# sokolov_control_board_2.net
KiCad netlist of a schematic drawn in Altium Designer
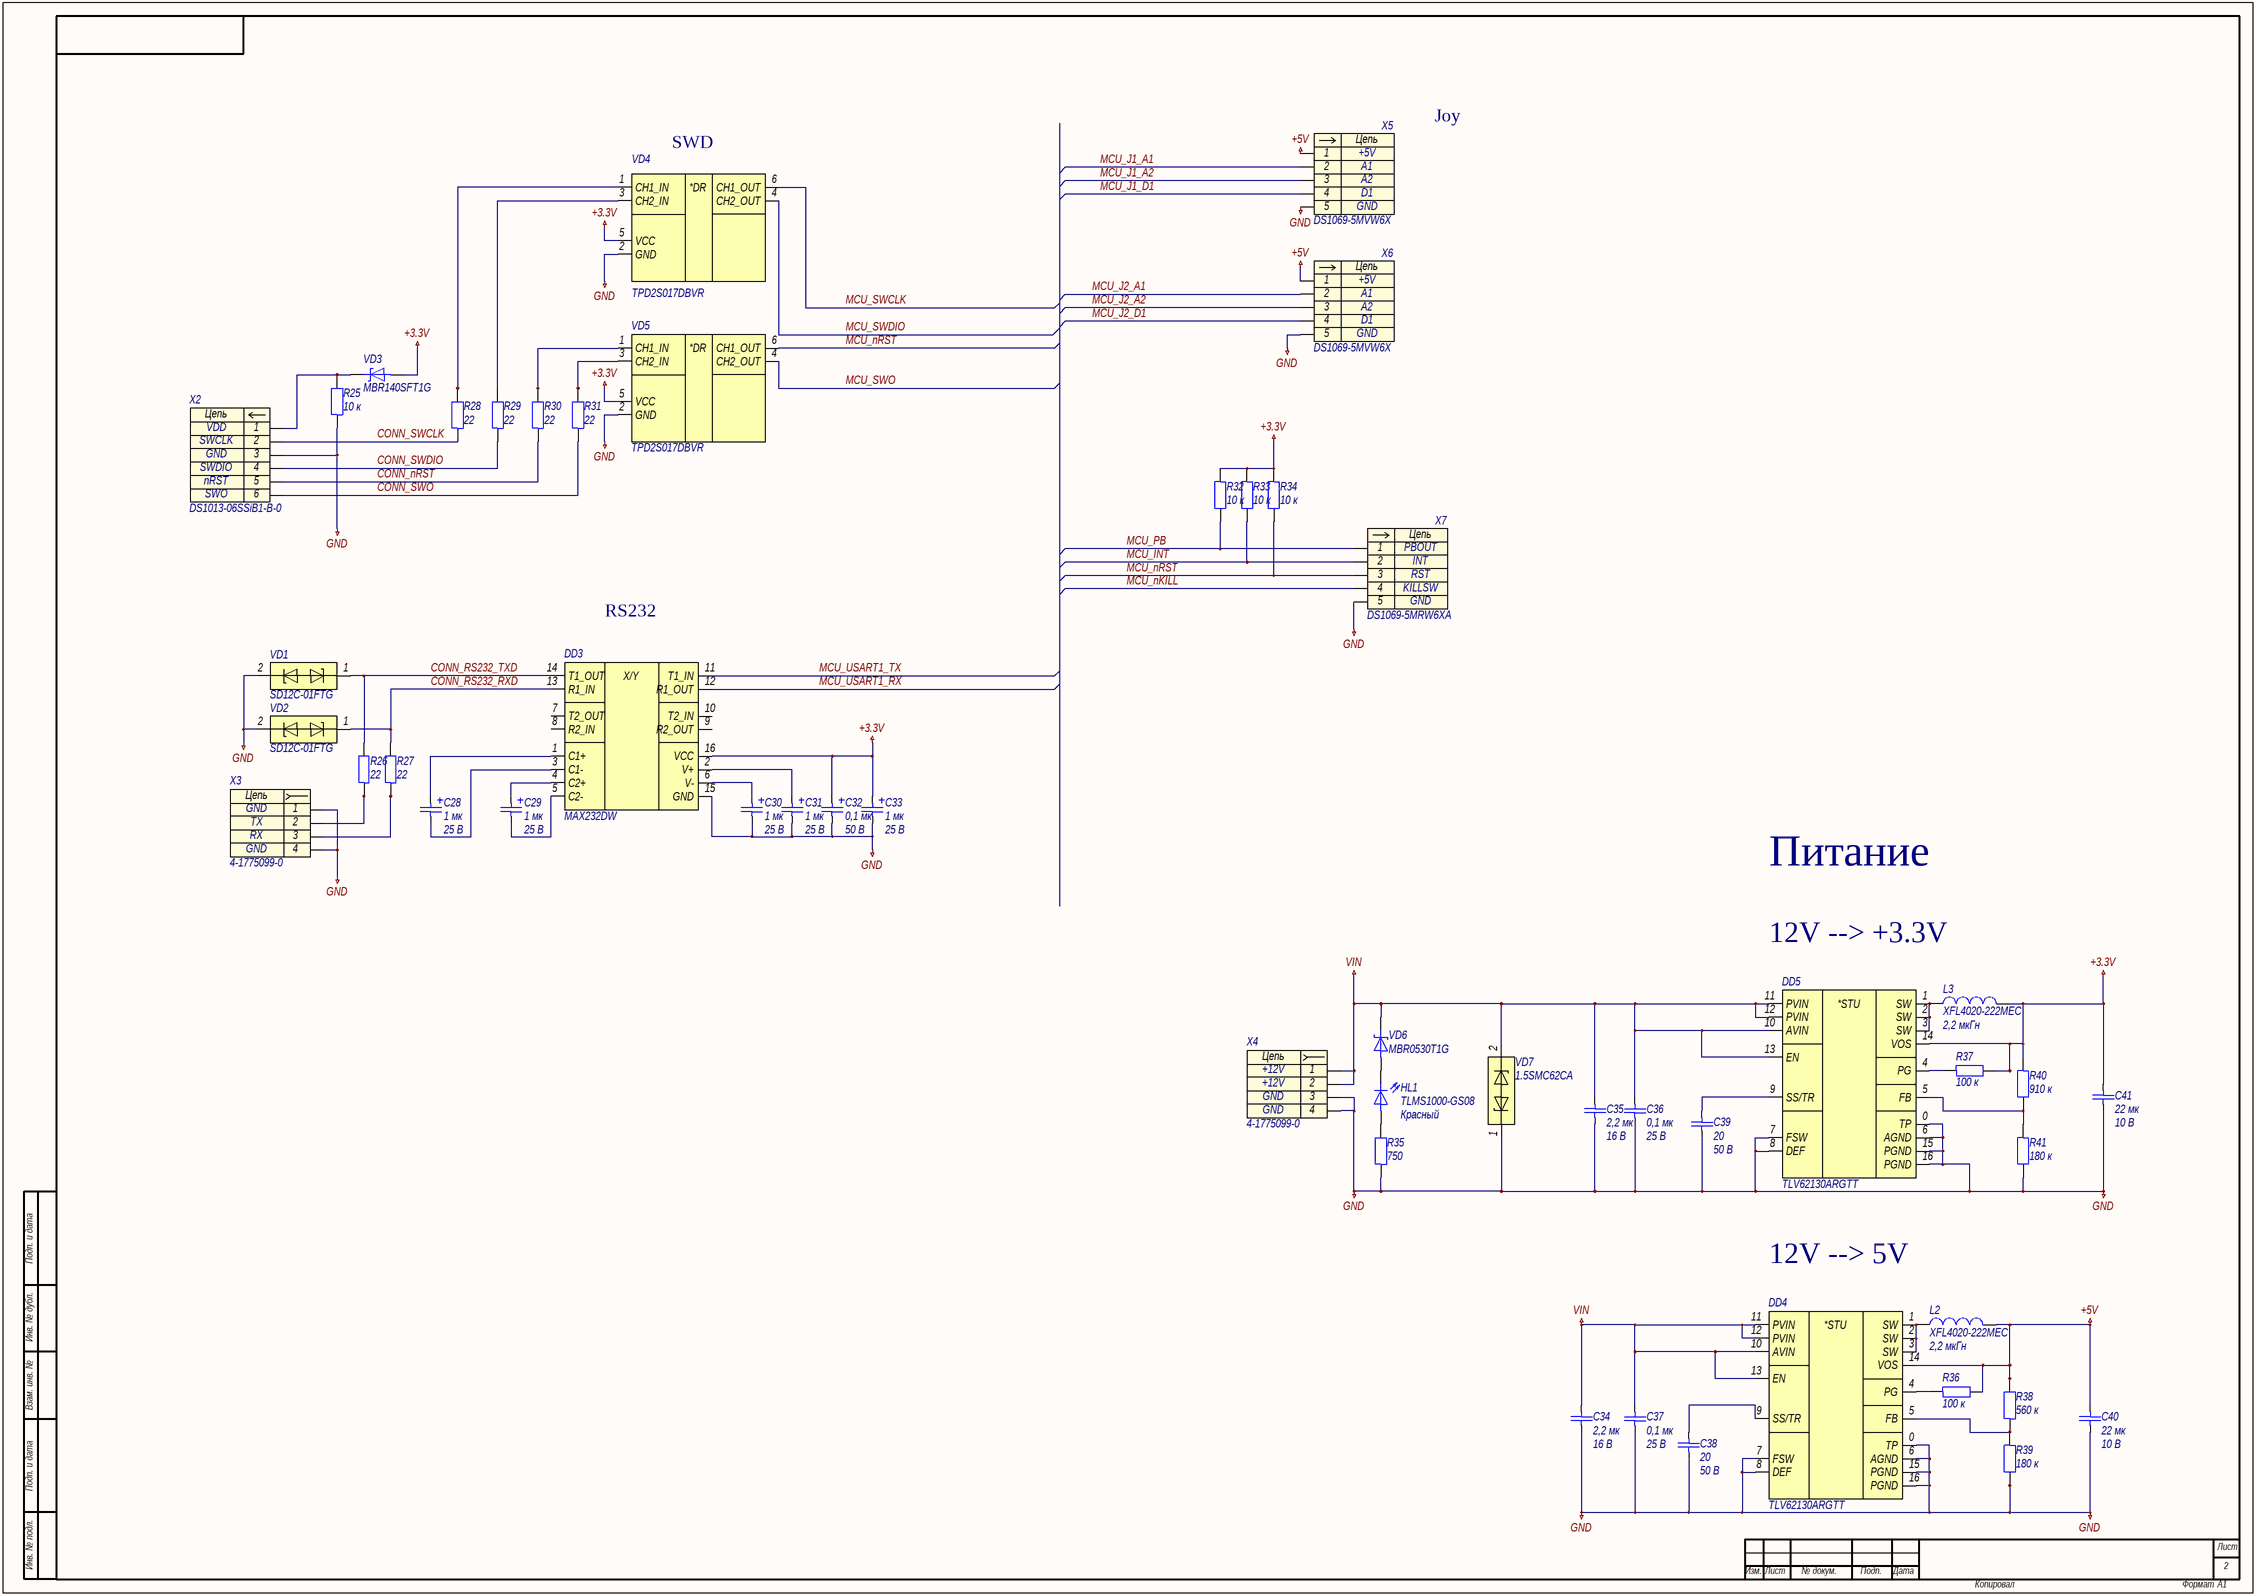
[diagram p0: sokolov_control_board_2.SchDoc]

(export (version "E")
  (design (tool "Eeschema 10.0.6"))
  (components
    (comp (ref "C28")
      (value "1 мк")
      (footprint "C3216-18")
      (description "=Описание")
      (fields (field (name "НАПРЯЖЕНИЕ") "25 В"))
      (libsource (lib "Database_Students") (part "CAPACITOR-POLAR"))
    )
    (comp (ref "C29")
      (value "1 мк")
      (footprint "C3216-18")
      (description "=Описание")
      (fields (field (name "НАПРЯЖЕНИЕ") "25 В"))
      (libsource (lib "Database_Students") (part "CAPACITOR-POLAR"))
    )
    (comp (ref "C30")
      (value "1 мк")
      (footprint "C3216-18")
      (description "=Описание")
      (fields (field (name "НАПРЯЖЕНИЕ") "25 В"))
      (libsource (lib "Database_Students") (part "CAPACITOR-POLAR"))
    )
    (comp (ref "C31")
      (value "1 мк")
      (footprint "C3216-18")
      (description "=Описание")
      (fields (field (name "НАПРЯЖЕНИЕ") "25 В"))
      (libsource (lib "Database_Students") (part "CAPACITOR-POLAR"))
    )
    (comp (ref "C32")
      (value "0,1 мк")
      (footprint "C3216-18")
      (description "=Описание")
      (fields (field (name "НАПРЯЖЕНИЕ") "50 В"))
      (libsource (lib "Database_Students") (part "CAPACITOR-POLAR"))
    )
    (comp (ref "C33")
      (value "1 мк")
      (footprint "C3216-18")
      (description "=Описание")
      (fields (field (name "НАПРЯЖЕНИЕ") "25 В"))
      (libsource (lib "Database_Students") (part "CAPACITOR-POLAR"))
    )
    (comp (ref "C34")
      (value "2,2 мк")
      (footprint "C0603")
      (description "=Описание")
      (fields (field (name "НАПРЯЖЕНИЕ") "16 В"))
      (libsource (lib "Database_Students") (part "CAPACITOR-NONPOLAR"))
    )
    (comp (ref "C35")
      (value "2,2 мк")
      (footprint "C0603")
      (description "=Описание")
      (fields (field (name "НАПРЯЖЕНИЕ") "16 В"))
      (libsource (lib "Database_Students") (part "CAPACITOR-NONPOLAR"))
    )
    (comp (ref "C36")
      (value "0,1 мк")
      (footprint "C0603")
      (description "=Описание")
      (fields (field (name "НАПРЯЖЕНИЕ") "25 В"))
      (libsource (lib "Database_Students") (part "CAPACITOR-NONPOLAR"))
    )
    (comp (ref "C37")
      (value "0,1 мк")
      (footprint "C0603")
      (description "=Описание")
      (fields (field (name "НАПРЯЖЕНИЕ") "25 В"))
      (libsource (lib "Database_Students") (part "CAPACITOR-NONPOLAR"))
    )
    (comp (ref "C38")
      (value "20")
      (footprint "C0603")
      (description "=Описание")
      (fields (field (name "НАПРЯЖЕНИЕ") "50 В"))
      (libsource (lib "Database_Students") (part "CAPACITOR-NONPOLAR"))
    )
    (comp (ref "C39")
      (value "20")
      (footprint "C0603")
      (description "=Описание")
      (fields (field (name "НАПРЯЖЕНИЕ") "50 В"))
      (libsource (lib "Database_Students") (part "CAPACITOR-NONPOLAR"))
    )
    (comp (ref "C40")
      (value "22 мк")
      (footprint "C1206")
      (description "=Описание")
      (fields (field (name "НАПРЯЖЕНИЕ") "10 В"))
      (libsource (lib "Database_Students") (part "CAPACITOR-NONPOLAR"))
    )
    (comp (ref "C41")
      (value "22 мк")
      (footprint "C1206")
      (description "=Описание")
      (fields (field (name "НАПРЯЖЕНИЕ") "10 В"))
      (libsource (lib "Database_Students") (part "CAPACITOR-NONPOLAR"))
    )
    (comp (ref "DD3")
      (value "MAX232DW")
      (footprint "SOIC-16-P127-1030X750X265-L84X41")
      (description "=Описание")
      (libsource (lib "Database_Students") (part "MAX232DW"))
    )
    (comp (ref "DD4")
      (value "TLV62130ARGTT")
      (footprint "WQFN-16-P50-300X300X100-L40X24-T168X168")
      (description "=Описание")
      (libsource (lib "Database_Students") (part "TLV62130ARGTT"))
    )
    (comp (ref "DD5")
      (value "TLV62130ARGTT")
      (footprint "WQFN-16-P50-300X300X100-L40X24-T168X168")
      (description "=Описание")
      (libsource (lib "Database_Students") (part "TLV62130ARGTT"))
    )
    (comp (ref "HL1")
      (value "TLMS1000-GS08")
      (footprint "HL0603")
      (description "=Описание")
      (fields (field (name "ЦВЕТ") "Красный"))
      (libsource (lib "Database_Students") (part "LED-COMMON"))
    )
    (comp (ref "L2")
      (value "XFL4020-222MEC")
      (footprint "XFL-2-400X400X210")
      (description "=Описание")
      (fields (field (name "ИНДУКТИВНОСТЬ") "2,2 мкГн"))
      (libsource (lib "Database_Students") (part "INDUCTOR-COMMON"))
    )
    (comp (ref "L3")
      (value "XFL4020-222MEC")
      (footprint "XFL-2-400X400X210")
      (description "=Описание")
      (fields (field (name "ИНДУКТИВНОСТЬ") "2,2 мкГн"))
      (libsource (lib "Database_Students") (part "INDUCTOR-COMMON"))
    )
    (comp (ref "R25")
      (value "10 к")
      (footprint "R0603")
      (description "=Описание")
      (libsource (lib "Database_Students") (part "RESISTOR-COMMON"))
    )
    (comp (ref "R26")
      (value "22")
      (footprint "R0603")
      (description "=Описание")
      (libsource (lib "Database_Students") (part "RESISTOR-COMMON"))
    )
    (comp (ref "R27")
      (value "22")
      (footprint "R0603")
      (description "=Описание")
      (libsource (lib "Database_Students") (part "RESISTOR-COMMON"))
    )
    (comp (ref "R28")
      (value "22")
      (footprint "R0603")
      (description "=Описание")
      (libsource (lib "Database_Students") (part "RESISTOR-COMMON"))
    )
    (comp (ref "R29")
      (value "22")
      (footprint "R0603")
      (description "=Описание")
      (libsource (lib "Database_Students") (part "RESISTOR-COMMON"))
    )
    (comp (ref "R30")
      (value "22")
      (footprint "R0603")
      (description "=Описание")
      (libsource (lib "Database_Students") (part "RESISTOR-COMMON"))
    )
    (comp (ref "R31")
      (value "22")
      (footprint "R0603")
      (description "=Описание")
      (libsource (lib "Database_Students") (part "RESISTOR-COMMON"))
    )
    (comp (ref "R32")
      (value "10 к")
      (footprint "R0603")
      (description "=Описание")
      (libsource (lib "Database_Students") (part "RESISTOR-COMMON"))
    )
    (comp (ref "R33")
      (value "10 к")
      (footprint "R0603")
      (description "=Описание")
      (libsource (lib "Database_Students") (part "RESISTOR-COMMON"))
    )
    (comp (ref "R34")
      (value "10 к")
      (footprint "R0603")
      (description "=Описание")
      (libsource (lib "Database_Students") (part "RESISTOR-COMMON"))
    )
    (comp (ref "R35")
      (value "750")
      (footprint "R0603")
      (description "=Описание")
      (libsource (lib "Database_Students") (part "RESISTOR-COMMON"))
    )
    (comp (ref "R36")
      (value "100 к")
      (footprint "R0603")
      (description "=Описание")
      (libsource (lib "Database_Students") (part "RESISTOR-COMMON"))
    )
    (comp (ref "R37")
      (value "100 к")
      (footprint "R0603")
      (description "=Описание")
      (libsource (lib "Database_Students") (part "RESISTOR-COMMON"))
    )
    (comp (ref "R38")
      (value "560 к")
      (footprint "R0603")
      (description "=Описание")
      (libsource (lib "Database_Students") (part "RESISTOR-COMMON"))
    )
    (comp (ref "R39")
      (value "180 к")
      (footprint "R0603")
      (description "=Описание")
      (libsource (lib "Database_Students") (part "RESISTOR-COMMON"))
    )
    (comp (ref "R40")
      (value "910 к")
      (footprint "R0603")
      (description "=Описание")
      (libsource (lib "Database_Students") (part "RESISTOR-COMMON"))
    )
    (comp (ref "R41")
      (value "180 к")
      (footprint "R0603")
      (description "=Описание")
      (libsource (lib "Database_Students") (part "RESISTOR-COMMON"))
    )
    (comp (ref "VD1")
      (value "SD12C-01FTG")
      (footprint "SOD-323-257X130X114")
      (description "=Описание")
      (libsource (lib "Database_Students") (part "ZENER-BI-DIRECTIONAL"))
    )
    (comp (ref "VD2")
      (value "SD12C-01FTG")
      (footprint "SOD-323-257X130X114")
      (description "=Описание")
      (libsource (lib "Database_Students") (part "ZENER-BI-DIRECTIONAL"))
    )
    (comp (ref "VD3")
      (value "MBR140SFT1G")
      (footprint "SOD-123FL-370X165X98")
      (description "=Описание")
      (libsource (lib "Database_Students") (part "DIODE-SCHOTTKY"))
    )
    (comp (ref "VD4")
      (value "TPD2S017DBVR")
      (footprint "SOT-23-6-P95-290X280X145")
      (description "=Описание")
      (libsource (lib "Database_Students") (part "TPD2S017DBVR"))
    )
    (comp (ref "VD5")
      (value "TPD2S017DBVR")
      (footprint "SOT-23-6-P95-290X280X145")
      (description "=Описание")
      (libsource (lib "Database_Students") (part "TPD2S017DBVR"))
    )
    (comp (ref "VD6")
      (value "MBR0530T1G")
      (footprint "SOD-123-368X160X135")
      (description "=Описание")
      (libsource (lib "Database_Students") (part "DIODE-SCHOTTKY"))
    )
    (comp (ref "VD7")
      (value "1.5SMC62CA")
      (footprint "DO-214AB-790X590X262")
      (description "=Описание")
      (libsource (lib "") (part "ZENER-BI-DIRECTIONAL_1"))
    )
    (comp (ref "X2")
      (value "DS1013-06SSiB1-B-0")
      (footprint "DS1013-06SSiB1-B-0")
      (description "=Описание")
      (libsource (lib "Database_Students") (part "HEADER-6-PLG"))
    )
    (comp (ref "X3")
      (value "4-1775099-0")
      (footprint "4-1775099-0")
      (description "=Описание")
      (libsource (lib "Database_Students") (part "HEADER-4-SCT"))
    )
    (comp (ref "X4")
      (value "4-1775099-0")
      (footprint "4-1775099-0")
      (description "=Описание")
      (libsource (lib "Database_Students") (part "HEADER-4-SCT"))
    )
    (comp (ref "X5")
      (value "DS1069-5MVW6X")
      (footprint "DS1069-5MVW6X")
      (description "=Описание")
      (libsource (lib "Database_Students") (part "HEADER-5-PLG"))
    )
    (comp (ref "X6")
      (value "DS1069-5MVW6X")
      (footprint "DS1069-5MVW6X")
      (description "=Описание")
      (libsource (lib "Database_Students") (part "HEADER-5-PLG"))
    )
    (comp (ref "X7")
      (value "DS1069-5MRW6XA")
      (footprint "DS1069-5MRW6XA")
      (description "=Описание")
      (libsource (lib "Database_Students") (part "HEADER-5-PLG"))
    )
  )
  (nets
    (net (code "1") (name "+3.3V") (class "Default")
      (node (ref "C32") (pin "1") (pinfunction "1_1") (pintype "passive"))
      (node (ref "C33") (pin "1") (pinfunction "1_1") (pintype "passive"))
      (node (ref "C41") (pin "2") (pinfunction "2_2") (pintype "passive"))
      (node (ref "DD3") (pin "16") (pinfunction "VCC_16") (pintype "passive"))
      (node (ref "DD5") (pin "14") (pinfunction "VOS_14") (pintype "passive"))
      (node (ref "L3") (pin "2") (pinfunction "2_2") (pintype "passive"))
      (node (ref "R32") (pin "1") (pinfunction "1_1") (pintype "passive"))
      (node (ref "R33") (pin "1") (pinfunction "1_1") (pintype "passive"))
      (node (ref "R34") (pin "1") (pinfunction "1_1") (pintype "passive"))
      (node (ref "R37") (pin "2") (pinfunction "2_2") (pintype "passive"))
      (node (ref "R40") (pin "1") (pinfunction "1_1") (pintype "passive"))
      (node (ref "VD3") (pin "2") (pinfunction "2_2") (pintype "passive"))
      (node (ref "VD4") (pin "5") (pinfunction "VCC_5") (pintype "passive"))
      (node (ref "VD5") (pin "5") (pinfunction "VCC_5") (pintype "passive"))
    )
    (net (code "2") (name "+5V") (class "Default")
      (node (ref "C40") (pin "2") (pinfunction "2_2") (pintype "passive"))
      (node (ref "DD4") (pin "14") (pinfunction "VOS_14") (pintype "passive"))
      (node (ref "L2") (pin "2") (pinfunction "2_2") (pintype "passive"))
      (node (ref "R36") (pin "2") (pinfunction "2_2") (pintype "passive"))
      (node (ref "R38") (pin "2") (pinfunction "2_2") (pintype "passive"))
      (node (ref "X5") (pin "1") (pinfunction "1_1") (pintype "passive"))
      (node (ref "X6") (pin "1") (pinfunction "1_1") (pintype "passive"))
    )
    (net (code "3") (name "/CONN_RS232_RXD") (class "Default")
      (node (ref "DD3") (pin "13") (pinfunction "R1_IN_13") (pintype "passive"))
      (node (ref "R27") (pin "2") (pinfunction "2_2") (pintype "passive"))
      (node (ref "VD2") (pin "1") (pinfunction "1_1") (pintype "passive"))
    )
    (net (code "4") (name "/CONN_RS232_TXD") (class "Default")
      (node (ref "DD3") (pin "14") (pinfunction "T1_OUT_14") (pintype "passive"))
      (node (ref "R26") (pin "2") (pinfunction "2_2") (pintype "passive"))
      (node (ref "VD1") (pin "1") (pinfunction "1_1") (pintype "passive"))
    )
    (net (code "5") (name "/CONN_SWCLK") (class "Default")
      (node (ref "R28") (pin "1") (pinfunction "1_1") (pintype "passive"))
      (node (ref "X2") (pin "2") (pinfunction "2_2") (pintype "passive"))
    )
    (net (code "6") (name "/CONN_SWDIO") (class "Default")
      (node (ref "R29") (pin "1") (pinfunction "1_1") (pintype "passive"))
      (node (ref "X2") (pin "4") (pinfunction "4_4") (pintype "passive"))
    )
    (net (code "7") (name "/CONN_SWO") (class "Default")
      (node (ref "R31") (pin "1") (pinfunction "1_1") (pintype "passive"))
      (node (ref "X2") (pin "6") (pinfunction "6_6") (pintype "passive"))
    )
    (net (code "8") (name "/CONN_nRST") (class "Default")
      (node (ref "R30") (pin "1") (pinfunction "1_1") (pintype "passive"))
      (node (ref "X2") (pin "5") (pinfunction "5_5") (pintype "passive"))
    )
    (net (code "9") (name "/MCU_INT") (class "Default")
      (node (ref "R33") (pin "2") (pinfunction "2_2") (pintype "passive"))
      (node (ref "X7") (pin "2") (pinfunction "2_2") (pintype "passive"))
    )
    (net (code "10") (name "/MCU_J1_A1") (class "Default")
      (node (ref "X5") (pin "2") (pinfunction "2_2") (pintype "passive"))
    )
    (net (code "11") (name "/MCU_J1_A2") (class "Default")
      (node (ref "X5") (pin "3") (pinfunction "3_3") (pintype "passive"))
    )
    (net (code "12") (name "/MCU_J1_D1") (class "Default")
      (node (ref "X5") (pin "4") (pinfunction "4_4") (pintype "passive"))
    )
    (net (code "13") (name "/MCU_J2_A1") (class "Default")
      (node (ref "X6") (pin "2") (pinfunction "2_2") (pintype "passive"))
    )
    (net (code "14") (name "/MCU_J2_A2") (class "Default")
      (node (ref "X6") (pin "3") (pinfunction "3_3") (pintype "passive"))
    )
    (net (code "15") (name "/MCU_J2_D1") (class "Default")
      (node (ref "X6") (pin "4") (pinfunction "4_4") (pintype "passive"))
    )
    (net (code "16") (name "/MCU_PB") (class "Default")
      (node (ref "R32") (pin "2") (pinfunction "2_2") (pintype "passive"))
      (node (ref "X7") (pin "1") (pinfunction "1_1") (pintype "passive"))
    )
    (net (code "17") (name "/MCU_SWCLK") (class "Default")
      (node (ref "VD4") (pin "6") (pinfunction "CH1_OUT_6") (pintype "passive"))
    )
    (net (code "18") (name "/MCU_SWDIO") (class "Default")
      (node (ref "VD4") (pin "4") (pinfunction "CH2_OUT_4") (pintype "passive"))
    )
    (net (code "19") (name "/MCU_SWO") (class "Default")
      (node (ref "VD5") (pin "4") (pinfunction "CH2_OUT_4") (pintype "passive"))
    )
    (net (code "20") (name "/MCU_USART1_RX") (class "Default")
      (node (ref "DD3") (pin "12") (pinfunction "R1_OUT_12") (pintype "passive"))
    )
    (net (code "21") (name "/MCU_USART1_TX") (class "Default")
      (node (ref "DD3") (pin "11") (pinfunction "T1_IN_11") (pintype "passive"))
    )
    (net (code "22") (name "/MCU_nKILL") (class "Default")
      (node (ref "X7") (pin "4") (pinfunction "4_4") (pintype "passive"))
    )
    (net (code "23") (name "/MCU_nRST") (class "Default")
      (node (ref "R34") (pin "2") (pinfunction "2_2") (pintype "passive"))
      (node (ref "VD5") (pin "6") (pinfunction "CH1_OUT_6") (pintype "passive"))
      (node (ref "X7") (pin "3") (pinfunction "3_3") (pintype "passive"))
    )
    (net (code "24") (name "GND") (class "Default")
      (node (ref "C30") (pin "2") (pinfunction "2_2") (pintype "passive"))
      (node (ref "C31") (pin "2") (pinfunction "2_2") (pintype "passive"))
      (node (ref "C32") (pin "2") (pinfunction "2_2") (pintype "passive"))
      (node (ref "C33") (pin "2") (pinfunction "2_2") (pintype "passive"))
      (node (ref "C34") (pin "1") (pinfunction "1_1") (pintype "passive"))
      (node (ref "C35") (pin "1") (pinfunction "1_1") (pintype "passive"))
      (node (ref "C36") (pin "2") (pinfunction "2_2") (pintype "passive"))
      (node (ref "C37") (pin "2") (pinfunction "2_2") (pintype "passive"))
      (node (ref "C38") (pin "1") (pinfunction "1_1") (pintype "passive"))
      (node (ref "C39") (pin "1") (pinfunction "1_1") (pintype "passive"))
      (node (ref "C40") (pin "1") (pinfunction "1_1") (pintype "passive"))
      (node (ref "C41") (pin "1") (pinfunction "1_1") (pintype "passive"))
      (node (ref "DD3") (pin "15") (pinfunction "GND_15") (pintype "passive"))
      (node (ref "DD4") (pin "0") (pinfunction "TP_0") (pintype "passive"))
      (node (ref "DD4") (pin "15") (pinfunction "PGND_15") (pintype "passive"))
      (node (ref "DD4") (pin "16") (pinfunction "PGND_16") (pintype "passive"))
      (node (ref "DD4") (pin "6") (pinfunction "AGND_6") (pintype "passive"))
      (node (ref "DD4") (pin "7") (pinfunction "FSW_7") (pintype "passive"))
      (node (ref "DD4") (pin "8") (pinfunction "DEF_8") (pintype "passive"))
      (node (ref "DD5") (pin "0") (pinfunction "TP_0") (pintype "passive"))
      (node (ref "DD5") (pin "15") (pinfunction "PGND_15") (pintype "passive"))
      (node (ref "DD5") (pin "16") (pinfunction "PGND_16") (pintype "passive"))
      (node (ref "DD5") (pin "6") (pinfunction "AGND_6") (pintype "passive"))
      (node (ref "DD5") (pin "7") (pinfunction "FSW_7") (pintype "passive"))
      (node (ref "DD5") (pin "8") (pinfunction "DEF_8") (pintype "passive"))
      (node (ref "R25") (pin "1") (pinfunction "1_1") (pintype "passive"))
      (node (ref "R35") (pin "1") (pinfunction "1_1") (pintype "passive"))
      (node (ref "R39") (pin "2") (pinfunction "2_2") (pintype "passive"))
      (node (ref "R41") (pin "2") (pinfunction "2_2") (pintype "passive"))
      (node (ref "VD1") (pin "2") (pinfunction "2_2") (pintype "passive"))
      (node (ref "VD2") (pin "2") (pinfunction "2_2") (pintype "passive"))
      (node (ref "VD4") (pin "2") (pinfunction "GND_2") (pintype "passive"))
      (node (ref "VD5") (pin "2") (pinfunction "GND_2") (pintype "passive"))
      (node (ref "VD7") (pin "1") (pinfunction "1_1") (pintype "passive"))
      (node (ref "X2") (pin "3") (pinfunction "3_3") (pintype "passive"))
      (node (ref "X3") (pin "1") (pinfunction "1_1") (pintype "passive"))
      (node (ref "X3") (pin "4") (pinfunction "4_4") (pintype "passive"))
      (node (ref "X4") (pin "3") (pinfunction "3_3") (pintype "passive"))
      (node (ref "X4") (pin "4") (pinfunction "4_4") (pintype "passive"))
      (node (ref "X5") (pin "5") (pinfunction "5_5") (pintype "passive"))
      (node (ref "X6") (pin "5") (pinfunction "5_5") (pintype "passive"))
      (node (ref "X7") (pin "5") (pinfunction "5_5") (pintype "passive"))
    )
    (net (code "25") (name "Net-(DD3-C1+)") (class "Default")
      (node (ref "C28") (pin "1") (pinfunction "1_1") (pintype "passive"))
      (node (ref "DD3") (pin "1") (pinfunction "C1+_1") (pintype "passive"))
    )
    (net (code "26") (name "Net-(DD3-C1-)") (class "Default")
      (node (ref "C28") (pin "2") (pinfunction "2_2") (pintype "passive"))
      (node (ref "DD3") (pin "3") (pinfunction "C1-_3") (pintype "passive"))
    )
    (net (code "27") (name "Net-(DD3-C2+)") (class "Default")
      (node (ref "C29") (pin "1") (pinfunction "1_1") (pintype "passive"))
      (node (ref "DD3") (pin "4") (pinfunction "C2+_4") (pintype "passive"))
    )
    (net (code "28") (name "Net-(DD3-C2-)") (class "Default")
      (node (ref "C29") (pin "2") (pinfunction "2_2") (pintype "passive"))
      (node (ref "DD3") (pin "5") (pinfunction "C2-_5") (pintype "passive"))
    )
    (net (code "29") (name "Net-(DD3-V+)") (class "Default")
      (node (ref "C31") (pin "1") (pinfunction "1_1") (pintype "passive"))
      (node (ref "DD3") (pin "2") (pinfunction "V+_2") (pintype "passive"))
    )
    (net (code "30") (name "Net-(DD3-V-)") (class "Default")
      (node (ref "C30") (pin "1") (pinfunction "1_1") (pintype "passive"))
      (node (ref "DD3") (pin "6") (pinfunction "V-_6") (pintype "passive"))
    )
    (net (code "31") (name "Net-(DD4-FB)") (class "Default")
      (node (ref "DD4") (pin "5") (pinfunction "FB_5") (pintype "passive"))
      (node (ref "R38") (pin "1") (pinfunction "1_1") (pintype "passive"))
      (node (ref "R39") (pin "1") (pinfunction "1_1") (pintype "passive"))
    )
    (net (code "32") (name "Net-(DD4-PG)") (class "Default")
      (node (ref "DD4") (pin "4") (pinfunction "PG_4") (pintype "passive"))
      (node (ref "R36") (pin "1") (pinfunction "1_1") (pintype "passive"))
    )
    (net (code "33") (name "Net-(DD4-SS{slash}TR)") (class "Default")
      (node (ref "C38") (pin "2") (pinfunction "2_2") (pintype "passive"))
      (node (ref "DD4") (pin "9") (pinfunction "SS/TR_9") (pintype "passive"))
    )
    (net (code "34") (name "Net-(DD4-SW-Pad1)") (class "Default")
      (node (ref "DD4") (pin "1") (pinfunction "SW_1") (pintype "passive"))
      (node (ref "DD4") (pin "2") (pinfunction "SW_2") (pintype "passive"))
      (node (ref "DD4") (pin "3") (pinfunction "SW_3") (pintype "passive"))
      (node (ref "L2") (pin "1") (pinfunction "1_1") (pintype "passive"))
    )
    (net (code "35") (name "Net-(DD5-FB)") (class "Default")
      (node (ref "DD5") (pin "5") (pinfunction "FB_5") (pintype "passive"))
      (node (ref "R40") (pin "2") (pinfunction "2_2") (pintype "passive"))
      (node (ref "R41") (pin "1") (pinfunction "1_1") (pintype "passive"))
    )
    (net (code "36") (name "Net-(DD5-PG)") (class "Default")
      (node (ref "DD5") (pin "4") (pinfunction "PG_4") (pintype "passive"))
      (node (ref "R37") (pin "1") (pinfunction "1_1") (pintype "passive"))
    )
    (net (code "37") (name "Net-(DD5-SS{slash}TR)") (class "Default")
      (node (ref "C39") (pin "2") (pinfunction "2_2") (pintype "passive"))
      (node (ref "DD5") (pin "9") (pinfunction "SS/TR_9") (pintype "passive"))
    )
    (net (code "38") (name "Net-(DD5-SW-Pad1)") (class "Default")
      (node (ref "DD5") (pin "1") (pinfunction "SW_1") (pintype "passive"))
      (node (ref "DD5") (pin "2") (pinfunction "SW_2") (pintype "passive"))
      (node (ref "DD5") (pin "3") (pinfunction "SW_3") (pintype "passive"))
      (node (ref "L3") (pin "1") (pinfunction "1_1") (pintype "passive"))
    )
    (net (code "39") (name "Net-(HL1-Pad1)") (class "Default")
      (node (ref "HL1") (pin "1") (pinfunction "1_1") (pintype "passive"))
      (node (ref "VD6") (pin "2") (pinfunction "2_2") (pintype "passive"))
    )
    (net (code "40") (name "Net-(HL1-Pad2)") (class "Default")
      (node (ref "HL1") (pin "2") (pinfunction "2_2") (pintype "passive"))
      (node (ref "R35") (pin "2") (pinfunction "2_2") (pintype "passive"))
    )
    (net (code "41") (name "Net-(R25-Pad2)") (class "Default")
      (node (ref "R25") (pin "2") (pinfunction "2_2") (pintype "passive"))
      (node (ref "VD3") (pin "1") (pinfunction "1_1") (pintype "passive"))
      (node (ref "X2") (pin "1") (pinfunction "1_1") (pintype "passive"))
    )
    (net (code "42") (name "Net-(R26-Pad1)") (class "Default")
      (node (ref "R26") (pin "1") (pinfunction "1_1") (pintype "passive"))
      (node (ref "X3") (pin "2") (pinfunction "2_2") (pintype "passive"))
    )
    (net (code "43") (name "Net-(R27-Pad1)") (class "Default")
      (node (ref "R27") (pin "1") (pinfunction "1_1") (pintype "passive"))
      (node (ref "X3") (pin "3") (pinfunction "3_3") (pintype "passive"))
    )
    (net (code "44") (name "Net-(VD4-CH1_IN)") (class "Default")
      (node (ref "R28") (pin "2") (pinfunction "2_2") (pintype "passive"))
      (node (ref "VD4") (pin "1") (pinfunction "CH1_IN_1") (pintype "passive"))
    )
    (net (code "45") (name "Net-(VD4-CH2_IN)") (class "Default")
      (node (ref "R29") (pin "2") (pinfunction "2_2") (pintype "passive"))
      (node (ref "VD4") (pin "3") (pinfunction "CH2_IN_3") (pintype "passive"))
    )
    (net (code "46") (name "Net-(VD5-CH1_IN)") (class "Default")
      (node (ref "R30") (pin "2") (pinfunction "2_2") (pintype "passive"))
      (node (ref "VD5") (pin "1") (pinfunction "CH1_IN_1") (pintype "passive"))
    )
    (net (code "47") (name "Net-(VD5-CH2_IN)") (class "Default")
      (node (ref "R31") (pin "2") (pinfunction "2_2") (pintype "passive"))
      (node (ref "VD5") (pin "3") (pinfunction "CH2_IN_3") (pintype "passive"))
    )
    (net (code "48") (name "VIN") (class "Default")
      (node (ref "C34") (pin "2") (pinfunction "2_2") (pintype "passive"))
      (node (ref "C35") (pin "2") (pinfunction "2_2") (pintype "passive"))
      (node (ref "C36") (pin "1") (pinfunction "1_1") (pintype "passive"))
      (node (ref "C37") (pin "1") (pinfunction "1_1") (pintype "passive"))
      (node (ref "DD4") (pin "10") (pinfunction "AVIN_10") (pintype "passive"))
      (node (ref "DD4") (pin "11") (pinfunction "PVIN_11") (pintype "passive"))
      (node (ref "DD4") (pin "12") (pinfunction "PVIN_12") (pintype "passive"))
      (node (ref "DD4") (pin "13") (pinfunction "EN_13") (pintype "passive"))
      (node (ref "DD5") (pin "10") (pinfunction "AVIN_10") (pintype "passive"))
      (node (ref "DD5") (pin "11") (pinfunction "PVIN_11") (pintype "passive"))
      (node (ref "DD5") (pin "12") (pinfunction "PVIN_12") (pintype "passive"))
      (node (ref "DD5") (pin "13") (pinfunction "EN_13") (pintype "passive"))
      (node (ref "VD6") (pin "1") (pinfunction "1_1") (pintype "passive"))
      (node (ref "VD7") (pin "2") (pinfunction "2_2") (pintype "passive"))
      (node (ref "X4") (pin "1") (pinfunction "1_1") (pintype "passive"))
      (node (ref "X4") (pin "2") (pinfunction "2_2") (pintype "passive"))
    )
    (net (code "49") (name "unconnected-(DD3-R2_IN-Pad8)") (class "Default")
      (node (ref "DD3") (pin "8") (pinfunction "R2_IN_8") (pintype "passive"))
    )
    (net (code "50") (name "unconnected-(DD3-R2_OUT-Pad9)") (class "Default")
      (node (ref "DD3") (pin "9") (pinfunction "R2_OUT_9") (pintype "passive"))
    )
    (net (code "51") (name "unconnected-(DD3-T2_IN-Pad10)") (class "Default")
      (node (ref "DD3") (pin "10") (pinfunction "T2_IN_10") (pintype "passive"))
    )
    (net (code "52") (name "unconnected-(DD3-T2_OUT-Pad7)") (class "Default")
      (node (ref "DD3") (pin "7") (pinfunction "T2_OUT_7") (pintype "passive"))
    )
  )
)
